# Input_Protection.net
KiCad netlist of a schematic drawn in Altium Designer
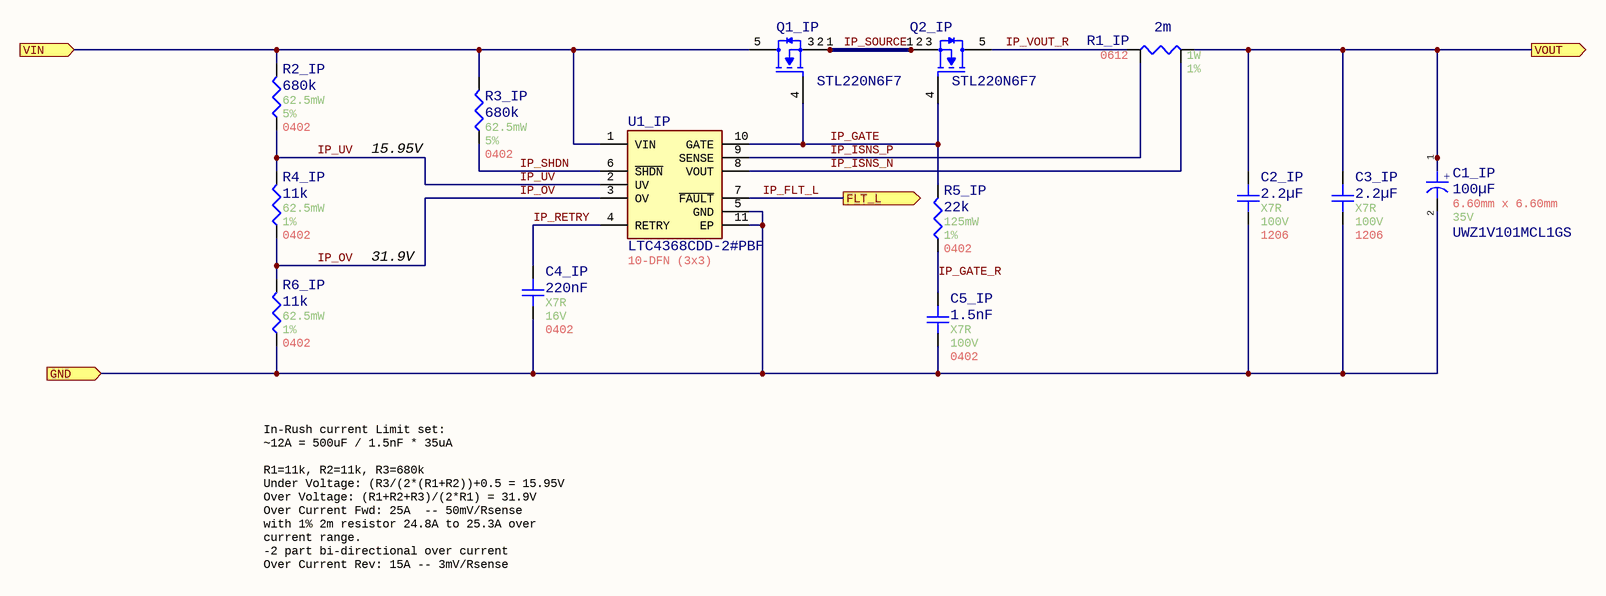
[diagram p0: Input_Protection.SchDoc]

(export (version "E")
  (design (tool "Eeschema 10.0.6"))
  (components
    (comp (ref "C1_IP")
      (value "UWZ1V101MCL1GS")
      (footprint "UWZ1V101MCL1GS")
      (fields
        (field (name "ALTIUM_VALUE") "100µF")
        (field (name "CASE/PACKAGE") "6.60mm x 6.60mm")
        (field (name "VOLTAGE RATING") "35V")
      )
      (libsource (lib "Raise Robotics") (part "Polarized Capacitor Pin1+"))
    )
    (comp (ref "C2_IP")
      (value "2.2µF")
      (footprint "Generic 1206 Capacitor")
      (fields
        (field (name "TEMPERATURE COEFFICIENT") "X7R")
        (field (name "VOLTAGE RATING") "100V")
        (field (name "CASE/PACKAGE") "1206")
        (field (name "TOLERANCE") "10%")
        (field (name "Comment") "12061C225K4T2A")
      )
      (libsource (lib "Raise Robotics") (part "Unpolarized Capacitor"))
    )
    (comp (ref "C3_IP")
      (value "2.2µF")
      (footprint "Generic 1206 Capacitor")
      (fields
        (field (name "TEMPERATURE COEFFICIENT") "X7R")
        (field (name "VOLTAGE RATING") "100V")
        (field (name "CASE/PACKAGE") "1206")
        (field (name "TOLERANCE") "10%")
        (field (name "Comment") "12061C225K4T2A")
      )
      (libsource (lib "Raise Robotics") (part "Unpolarized Capacitor"))
    )
    (comp (ref "C4_IP")
      (value "220nF")
      (footprint "Generic 0402 capacitor")
      (fields
        (field (name "TEMPERATURE COEFFICIENT") "X7R")
        (field (name "VOLTAGE RATING") "16V")
        (field (name "CASE/PACKAGE") "0402")
        (field (name "TOLERANCE") "20%")
        (field (name "Comment") "GCM155R71C224ME02D")
      )
      (libsource (lib "Raise Robotics") (part "Unpolarized Capacitor"))
    )
    (comp (ref "C5_IP")
      (value "1.5nF")
      (footprint "Generic 0402 capacitor")
      (fields
        (field (name "TEMPERATURE COEFFICIENT") "X7R")
        (field (name "VOLTAGE RATING") "100V")
        (field (name "CASE/PACKAGE") "0402")
        (field (name "TOLERANCE") "10%")
        (field (name "Comment") "GCM155R72A152KA37D")
      )
      (libsource (lib "Raise Robotics") (part "Unpolarized Capacitor"))
    )
    (comp (ref "Q1_IP")
      (value "STL220N6F7")
      (footprint "STL220N6F7")
      (fields (field (name "POWER") "4.8W"))
      (libsource (lib "Raise Robotics") (part "LFPAK56, Power-SO8"))
    )
    (comp (ref "Q2_IP")
      (value "STL220N6F7")
      (footprint "STL220N6F7")
      (fields (field (name "POWER") "4.8W"))
      (libsource (lib "Raise Robotics") (part "LFPAK56, Power-SO8"))
    )
    (comp (ref "R1_IP")
      (value "2m")
      (footprint "FP-WSKW0612-MFG")
      (description "Fixed Resistor, Metal Strip, 1W, 0.002ohm, 0.045V, 1% +/-Tol, 150ppm/Cel, Surface Mount, 0612")
      (fields
        (field (name "POWER") "1W")
        (field (name "TOLERANCE") "1%")
        (field (name "CASE/PACKAGE") "0612")
        (field (name "MANUFACTURER PART NUMBER") "TFA0805R60R4F-T5")
        (field (name "Comment") "WSKW06122L000FEA")
      )
      (libsource (lib "Raise Robotics") (part "Copy of Resistor"))
    )
    (comp (ref "R2_IP")
      (value "680k")
      (footprint "Generic 0402 Resistor")
      (fields
        (field (name "POWER") "62.5mW")
        (field (name "TOLERANCE") "5%")
        (field (name "CASE/PACKAGE") "0402")
        (field (name "Comment") "AC0402JR-07680KL")
      )
      (libsource (lib "Raise Robotics") (part "Resistor"))
    )
    (comp (ref "R3_IP")
      (value "680k")
      (footprint "Generic 0402 Resistor")
      (fields
        (field (name "POWER") "62.5mW")
        (field (name "TOLERANCE") "5%")
        (field (name "CASE/PACKAGE") "0402")
        (field (name "Comment") "AC0402JR-07680KL")
      )
      (libsource (lib "Raise Robotics") (part "Resistor"))
    )
    (comp (ref "R4_IP")
      (value "11k")
      (footprint "Generic 0402 Resistor")
      (description "Res Thick Film 0402 11K Ohm 1% 0.063W(1/16W) ±100ppm/C Pad SMD Automotive T/R")
      (fields
        (field (name "POWER") "62.5mW")
        (field (name "TOLERANCE") "1%")
        (field (name "CASE/PACKAGE") "0402")
        (field (name "Comment") "RMCF0402FT11K0")
      )
      (libsource (lib "Raise Robotics") (part "Resistor"))
    )
    (comp (ref "R5_IP")
      (value "22k")
      (footprint "Generic 0402 Resistor")
      (fields
        (field (name "POWER") "125mW")
        (field (name "TOLERANCE") "1%")
        (field (name "CASE/PACKAGE") "0402")
        (field (name "MANUFACTURER PART NUMBER") "AC0402FR-7W22KL")
      )
      (libsource (lib "Raise Robotics") (part "Resistor"))
    )
    (comp (ref "R6_IP")
      (value "11k")
      (footprint "Generic 0402 Resistor")
      (description "Res Thick Film 0402 11K Ohm 1% 0.063W(1/16W) ±100ppm/C Pad SMD Automotive T/R")
      (fields
        (field (name "POWER") "62.5mW")
        (field (name "TOLERANCE") "1%")
        (field (name "CASE/PACKAGE") "0402")
        (field (name "Comment") "RMCF0402FT11K0")
      )
      (libsource (lib "Raise Robotics") (part "Resistor"))
    )
    (comp (ref "U1_IP")
      (value "LTC4368CDD-2#PBF")
      (footprint "DFN-10_3x3x0.8mm_P0.5mm")
      (description "100V UV/OV and Reverse Protection Controller with Bidirectional Circuit Breaker")
      (fields (field (name "MPN") "LTC4368CMS-1#PBF") (field (name "CASE/PACKAGE") "10-DFN (3x3)"))
      (libsource (lib "Raise Robotics") (part "LTC4368CDD-2#PBF"))
    )
  )
  (nets
    (net (code "1") (name "/GND") (class "Default")
      (node (ref "C1_IP") (pin "2") (pinfunction "2_2") (pintype "passive"))
      (node (ref "C2_IP") (pin "1") (pinfunction "1_1") (pintype "passive"))
      (node (ref "C3_IP") (pin "1") (pinfunction "1_1") (pintype "passive"))
      (node (ref "C4_IP") (pin "1") (pinfunction "1_1") (pintype "passive"))
      (node (ref "C5_IP") (pin "1") (pinfunction "1_1") (pintype "passive"))
      (node (ref "R6_IP") (pin "1") (pinfunction "1_1") (pintype "passive"))
      (node (ref "U1_IP") (pin "11") (pinfunction "EP_11") (pintype "passive"))
      (node (ref "U1_IP") (pin "5") (pinfunction "GND_5") (pintype "passive"))
    )
    (net (code "2") (name "/IP_FLT_L") (class "Default")
      (node (ref "U1_IP") (pin "7") (pinfunction "~{FAULT}_7") (pintype "passive"))
    )
    (net (code "3") (name "/IP_GATE") (class "Default")
      (node (ref "Q1_IP") (pin "4") (pinfunction "GATE_4") (pintype "passive"))
      (node (ref "Q2_IP") (pin "4") (pinfunction "GATE_4") (pintype "passive"))
      (node (ref "R5_IP") (pin "2") (pinfunction "2_2") (pintype "passive"))
      (node (ref "U1_IP") (pin "10") (pinfunction "GATE_10") (pintype "passive"))
    )
    (net (code "4") (name "/IP_GATE_R") (class "Default")
      (node (ref "C5_IP") (pin "2") (pinfunction "2_2") (pintype "passive"))
      (node (ref "R5_IP") (pin "1") (pinfunction "1_1") (pintype "passive"))
    )
    (net (code "5") (name "/IP_ISNS_N") (class "Default")
      (node (ref "R1_IP") (pin "S2") (pinfunction "S2_S2") (pintype "passive"))
      (node (ref "U1_IP") (pin "8") (pinfunction "VOUT_8") (pintype "passive"))
    )
    (net (code "6") (name "/IP_ISNS_P") (class "Default")
      (node (ref "R1_IP") (pin "S1") (pinfunction "S1_S1") (pintype "passive"))
      (node (ref "U1_IP") (pin "9") (pinfunction "SENSE_9") (pintype "passive"))
    )
    (net (code "7") (name "/IP_OV") (class "Default")
      (node (ref "R4_IP") (pin "1") (pinfunction "1_1") (pintype "passive"))
      (node (ref "R6_IP") (pin "2") (pinfunction "2_2") (pintype "passive"))
      (node (ref "U1_IP") (pin "3") (pinfunction "OV_3") (pintype "passive"))
    )
    (net (code "8") (name "/IP_RETRY") (class "Default")
      (node (ref "C4_IP") (pin "2") (pinfunction "2_2") (pintype "passive"))
      (node (ref "U1_IP") (pin "4") (pinfunction "RETRY_4") (pintype "passive"))
    )
    (net (code "9") (name "/IP_SHDN") (class "Default")
      (node (ref "R3_IP") (pin "1") (pinfunction "1_1") (pintype "passive"))
      (node (ref "U1_IP") (pin "6") (pinfunction "~{SHDN}_6") (pintype "passive"))
    )
    (net (code "10") (name "/IP_SOURCE") (class "Default")
      (node (ref "Q1_IP") (pin "1") (pinfunction "SOURCE_1") (pintype "passive"))
      (node (ref "Q1_IP") (pin "2") (pinfunction "SOURCE_2") (pintype "passive"))
      (node (ref "Q1_IP") (pin "3") (pinfunction "SOURCE_3") (pintype "passive"))
      (node (ref "Q2_IP") (pin "1") (pinfunction "SOURCE_1") (pintype "passive"))
      (node (ref "Q2_IP") (pin "2") (pinfunction "SOURCE_2") (pintype "passive"))
      (node (ref "Q2_IP") (pin "3") (pinfunction "SOURCE_3") (pintype "passive"))
    )
    (net (code "11") (name "/IP_UV") (class "Default")
      (node (ref "R2_IP") (pin "1") (pinfunction "1_1") (pintype "passive"))
      (node (ref "R4_IP") (pin "2") (pinfunction "2_2") (pintype "passive"))
      (node (ref "U1_IP") (pin "2") (pinfunction "UV_2") (pintype "passive"))
    )
    (net (code "12") (name "/IP_VOUT_R") (class "Default")
      (node (ref "Q2_IP") (pin "5") (pinfunction "DRAIN_5") (pintype "passive"))
      (node (ref "R1_IP") (pin "1") (pinfunction "1_1") (pintype "passive"))
    )
    (net (code "13") (name "/VIN") (class "Default")
      (node (ref "Q1_IP") (pin "5") (pinfunction "DRAIN_5") (pintype "passive"))
      (node (ref "R2_IP") (pin "2") (pinfunction "2_2") (pintype "passive"))
      (node (ref "R3_IP") (pin "2") (pinfunction "2_2") (pintype "passive"))
      (node (ref "U1_IP") (pin "1") (pinfunction "VIN_1") (pintype "passive"))
    )
    (net (code "14") (name "/VOUT") (class "Default")
      (node (ref "C1_IP") (pin "1") (pinfunction "1_1") (pintype "passive"))
      (node (ref "C2_IP") (pin "2") (pinfunction "2_2") (pintype "passive"))
      (node (ref "C3_IP") (pin "2") (pinfunction "2_2") (pintype "passive"))
      (node (ref "R1_IP") (pin "2") (pinfunction "2_2") (pintype "passive"))
    )
  )
)
